# SCH_hackercard_2026-05-06.net
KiCad netlist of a schematic drawn in EasyEDA
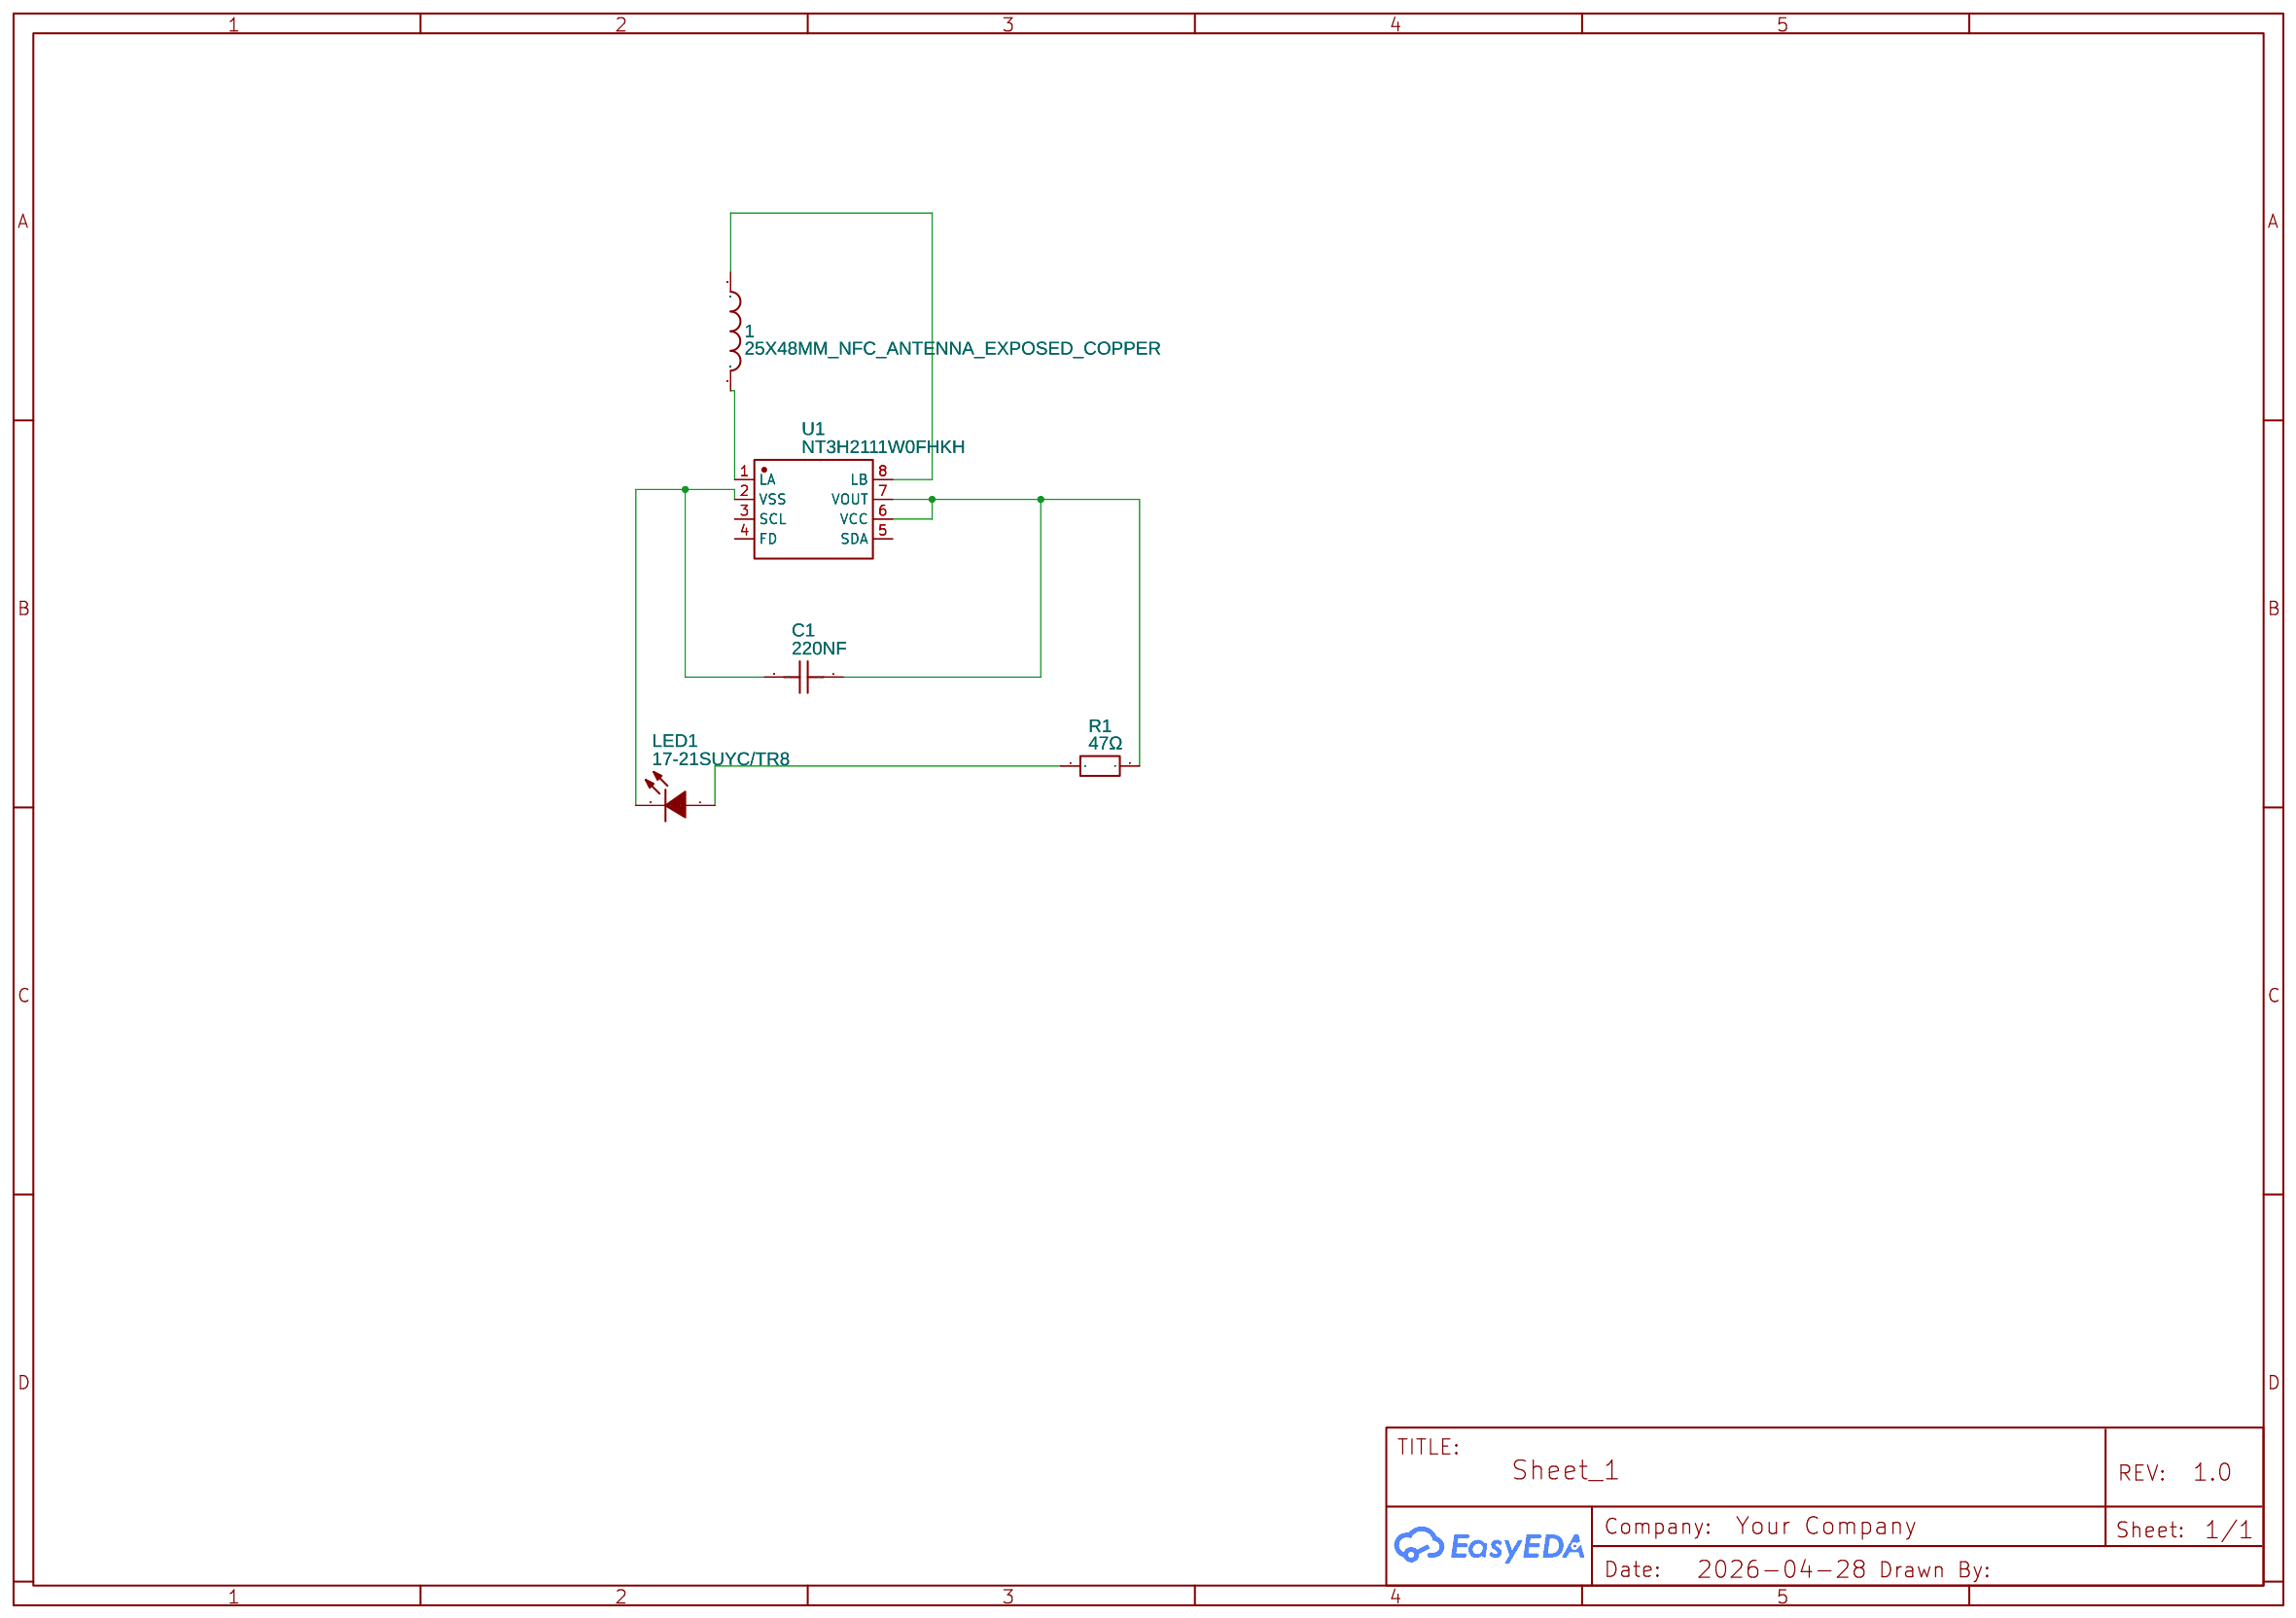
[diagram p0: schematic sheet]

(export (version "E")
  (design (tool "Eeschema 10.0.6"))
  (components
    (comp (ref "1")
      (value "25X48MM_NFC_ANTENNA_EXPOSED_COPPER")
      (libsource (lib "") (part "25X48MM_NFC_ANTENNA_EXPOSED_COPPER"))
    )
    (comp (ref "C1")
      (value "220NF")
      (fields (field (name "Manufacturer Part") "220nF"))
      (libsource (lib "") (part "220NF"))
    )
    (comp (ref "LED1")
      (value "17-21SUYC/TR8")
      (fields (field (name "Manufacturer Part") "KT-0805黄灯") (field (name "Manufacturer") "KENTO"))
      (libsource (lib "") (part "17-21SUYC/TR8"))
    )
    (comp (ref "R1")
      (value "47Ω")
      (fields (field (name "Manufacturer Part") "RC2512FK-7W16RL") (field (name "Manufacturer") "YAGEO(国巨)"))
      (libsource (lib "") (part "RC2512FK-7W16RL"))
    )
    (comp (ref "U1")
      (value "NT3H2111W0FHKH")
      (fields (field (name "Manufacturer") "NXP(恩智浦)"))
      (libsource (lib "") (part "NT3H2111W0FHKH"))
    )
  )
  (nets
    (net (code "1") (name "Net-(LED1-+)") (class "Default")
      (node (ref "LED1") (pin "1") (pinfunction "+_1") (pintype "unspecified"))
      (node (ref "R1") (pin "1") (pinfunction "1_1") (pintype "unspecified"))
    )
    (net (code "2") (name "Net-(LED1--)") (class "Default")
      (node (ref "C1") (pin "2") (pinfunction "2_2") (pintype "unspecified"))
      (node (ref "LED1") (pin "2") (pinfunction "-_2") (pintype "unspecified"))
      (node (ref "U1") (pin "2") (pinfunction "VSS_2") (pintype "unspecified"))
    )
    (net (code "3") (name "Net-(U1-LA)") (class "Default")
      (node (ref "1") (pin "P$2") (pinfunction "P$2_P$2") (pintype "bidirectional"))
      (node (ref "U1") (pin "1") (pinfunction "LA_1") (pintype "unspecified"))
    )
    (net (code "4") (name "Net-(U1-LB)") (class "Default")
      (node (ref "1") (pin "P$1") (pinfunction "P$1_P$1") (pintype "bidirectional"))
      (node (ref "U1") (pin "8") (pinfunction "LB_8") (pintype "unspecified"))
    )
    (net (code "5") (name "Net-(U1-VCC)") (class "Default")
      (node (ref "C1") (pin "1") (pinfunction "1_1") (pintype "unspecified"))
      (node (ref "R1") (pin "2") (pinfunction "2_2") (pintype "unspecified"))
      (node (ref "U1") (pin "6") (pinfunction "VCC_6") (pintype "unspecified"))
      (node (ref "U1") (pin "7") (pinfunction "VOUT_7") (pintype "unspecified"))
    )
    (net (code "6") (name "unconnected-(U1-FD-Pad4)") (class "Default")
      (node (ref "U1") (pin "4") (pinfunction "FD_4") (pintype "unspecified"))
    )
    (net (code "7") (name "unconnected-(U1-SCL-Pad3)") (class "Default")
      (node (ref "U1") (pin "3") (pinfunction "SCL_3") (pintype "unspecified"))
    )
    (net (code "8") (name "unconnected-(U1-SDA-Pad5)") (class "Default")
      (node (ref "U1") (pin "5") (pinfunction "SDA_5") (pintype "unspecified"))
    )
  )
)
